# LB_BIT_i5_SLIDEDIMMER-v03_3_3.net
KiCad netlist of a schematic drawn in EAGLE
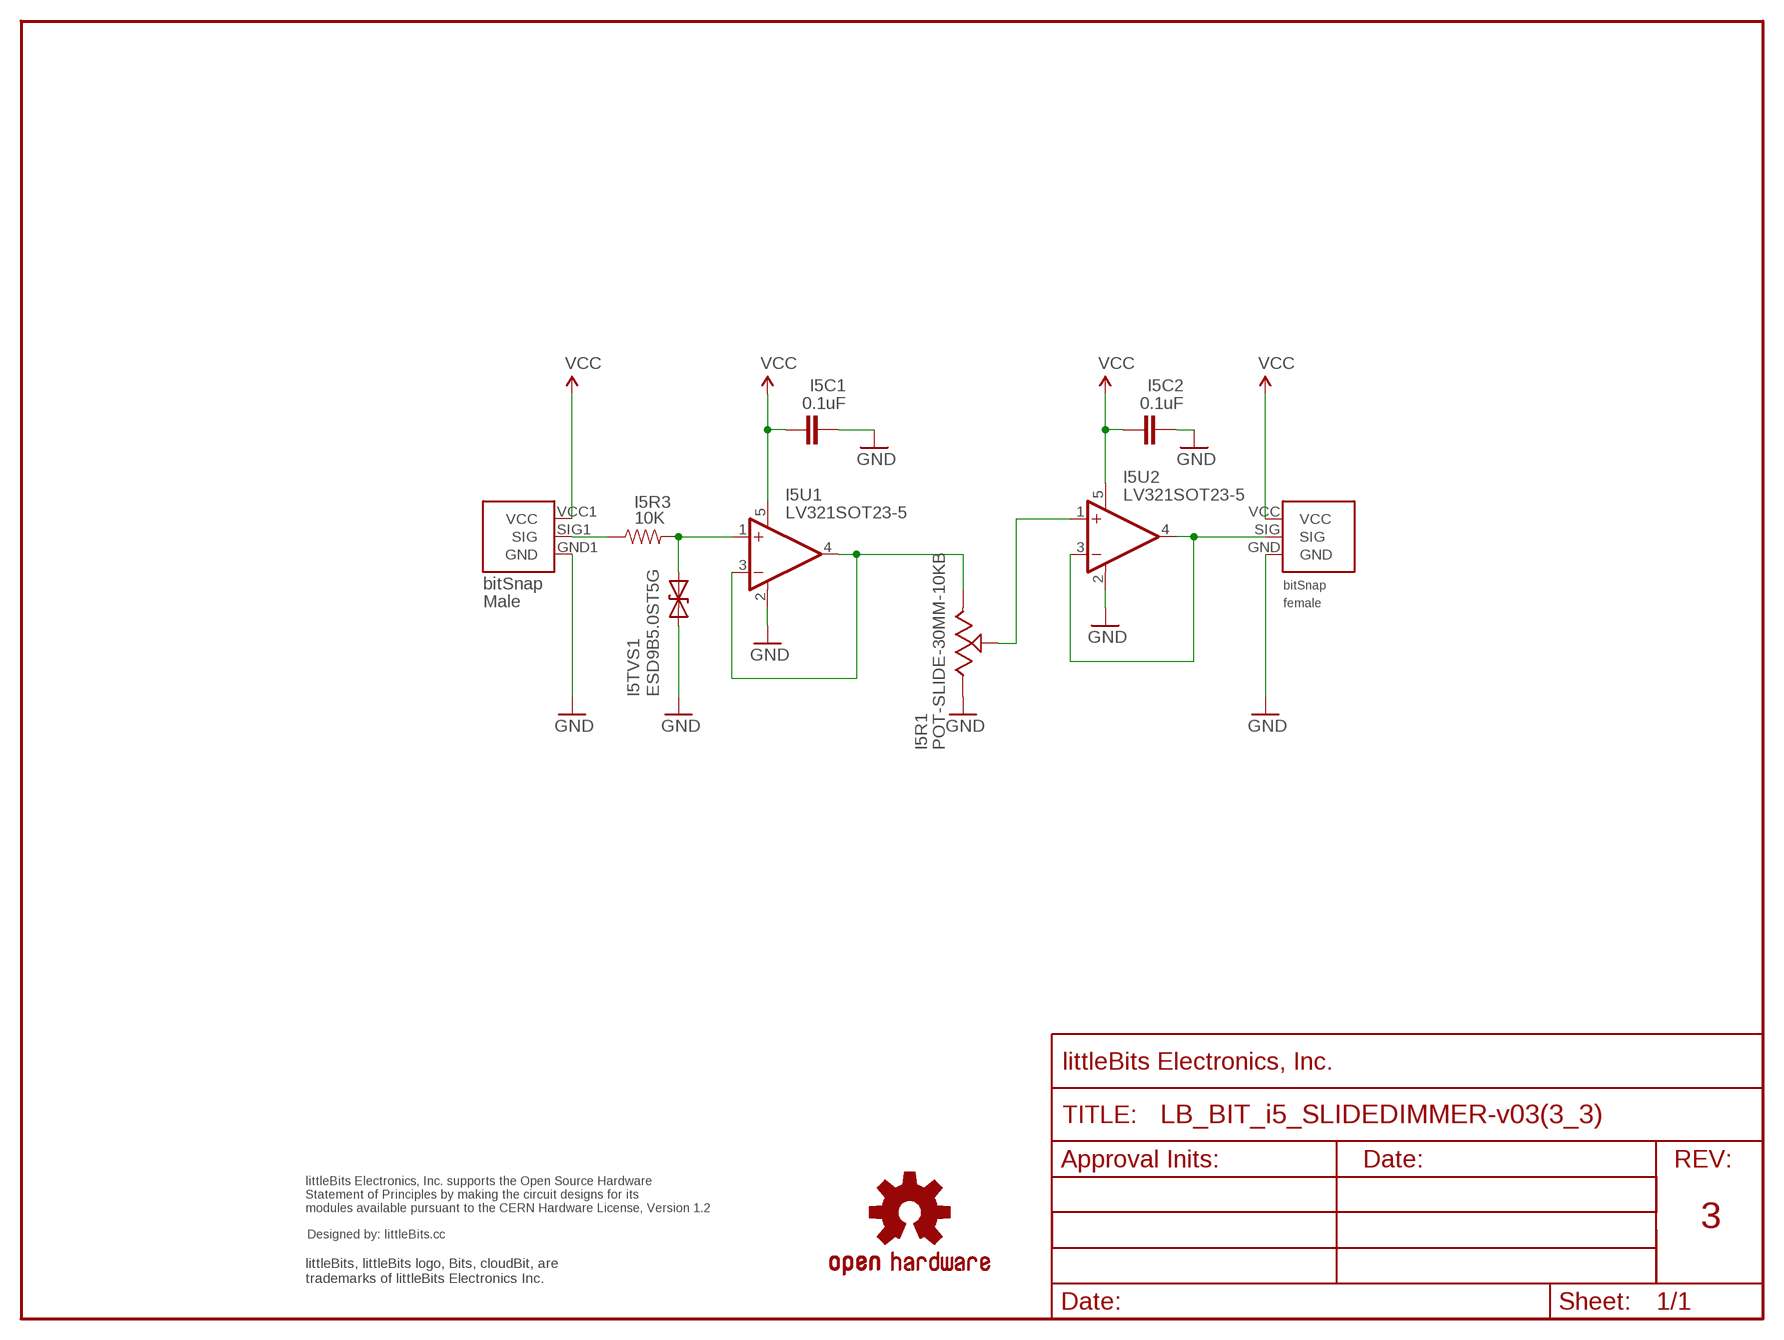
[diagram p0: schematic, sheet 1]

(export (version "E")
  (design (tool "Eeschema 10.0.6"))
  (components
    (comp (ref "FRAME2")
      (value "FRAME-LETTER-OHWOHW")
      (footprint "eagle-import:FABDWG01-OHW")
      (libsource (lib "eagle-import") (part "FRAME-LETTER-OHWOHW"))
    )
    (comp (ref "I5BSF1")
      (value "BITSNAP_V03_FEMALE")
      (footprint "eagle-import:BITSNAP_V03_FEMALE")
      (libsource (lib "eagle-import") (part "BITSNAP_V03_FEMALE"))
    )
    (comp (ref "I5BSM1")
      (value "BITSNAP_V03_MALE")
      (footprint "eagle-import:BITSNAP_V03_MALE")
      (libsource (lib "eagle-import") (part "BITSNAP_V03_MALE"))
    )
    (comp (ref "I5C1")
      (value "0.1uF")
      (footprint "eagle-import:CAP-0603")
      (libsource (lib "eagle-import") (part "CAPCAP-0603"))
    )
    (comp (ref "I5C2")
      (value "0.1uF")
      (footprint "eagle-import:CAP-0603")
      (libsource (lib "eagle-import") (part "CAPCAP-0603"))
    )
    (comp (ref "I5R1")
      (value "POT-SLIDE-30MM-10KB")
      (footprint "eagle-import:POT-SLIDE-30MM")
      (libsource (lib "eagle-import") (part "POT-SLIDE-30MM"))
    )
    (comp (ref "I5R3")
      (value "10K")
      (footprint "eagle-import:RES-0603")
      (libsource (lib "eagle-import") (part "RES-0603"))
    )
    (comp (ref "I5TVS1")
      (value "ESD9B5.0ST5G")
      (footprint "eagle-import:SOD-923")
      (libsource (lib "eagle-import") (part "DIODE-TVSSOD-923"))
    )
    (comp (ref "I5U1")
      (value "LV321SOT23-5")
      (footprint "eagle-import:SOT23-5")
      (libsource (lib "eagle-import") (part "LV321SOT23-5"))
    )
    (comp (ref "I5U2")
      (value "LV321SOT23-5")
      (footprint "eagle-import:SOT23-5")
      (libsource (lib "eagle-import") (part "LV321SOT23-5"))
    )
    (comp (ref "U$1")
      (value "OSHWCREDIT")
      (footprint "eagle-import:OSHWCREDIT")
      (libsource (lib "eagle-import") (part "OSHWCREDIT"))
    )
    (comp (ref "U$5")
      (value "OSHW-LOGOL")
      (footprint "eagle-import:OSHW-LOGO-L")
      (libsource (lib "eagle-import") (part "OSHW-LOGOL"))
    )
  )
  (nets
    (net (code "1") (name "GND") (class "Default")
      (node (ref "I5BSF1") (pin "GND") (pinfunction "GND_GND") (pintype "bidirectional"))
      (node (ref "I5BSM1") (pin "GND1") (pinfunction "GND_GND1") (pintype "bidirectional"))
      (node (ref "I5C1") (pin "2") (pinfunction "2_2") (pintype "passive"))
      (node (ref "I5C2") (pin "2") (pinfunction "2_2") (pintype "passive"))
      (node (ref "I5R1") (pin "3") (pinfunction "3_3") (pintype "passive"))
      (node (ref "I5TVS1") (pin "1") (pinfunction "A_1") (pintype "passive"))
      (node (ref "I5U1") (pin "2") (pinfunction "V-_2") (pintype "power_in"))
      (node (ref "I5U2") (pin "2") (pinfunction "V-_2") (pintype "power_in"))
    )
    (net (code "2") (name "Net-(I5BSM1-SIG)") (class "Default")
      (node (ref "I5BSM1") (pin "SIG1") (pinfunction "SIG_SIG1") (pintype "bidirectional"))
      (node (ref "I5R3") (pin "1") (pinfunction "1_1") (pintype "passive"))
    )
    (net (code "3") (name "Net-(I5TVS1-C)") (class "Default")
      (node (ref "I5R3") (pin "2") (pinfunction "2_2") (pintype "passive"))
      (node (ref "I5TVS1") (pin "2") (pinfunction "C_2") (pintype "passive"))
      (node (ref "I5U1") (pin "1") (pinfunction "+IN_1") (pintype "input"))
    )
    (net (code "4") (name "Net-(I5U1--IN)") (class "Default")
      (node (ref "I5R1") (pin "1") (pinfunction "1_1") (pintype "passive"))
      (node (ref "I5U1") (pin "3") (pinfunction "-IN_3") (pintype "input"))
      (node (ref "I5U1") (pin "4") (pinfunction "OUT_4") (pintype "output"))
    )
    (net (code "5") (name "Net-(I5U2-+IN)") (class "Default")
      (node (ref "I5R1") (pin "2") (pinfunction "2_2") (pintype "passive"))
      (node (ref "I5U2") (pin "1") (pinfunction "+IN_1") (pintype "input"))
    )
    (net (code "6") (name "Net-(I5U2--IN)") (class "Default")
      (node (ref "I5BSF1") (pin "SIG") (pinfunction "SIG_SIG") (pintype "bidirectional"))
      (node (ref "I5U2") (pin "3") (pinfunction "-IN_3") (pintype "input"))
      (node (ref "I5U2") (pin "4") (pinfunction "OUT_4") (pintype "output"))
    )
    (net (code "7") (name "VCC") (class "Default")
      (node (ref "I5BSF1") (pin "VCC") (pinfunction "VCC_VCC") (pintype "bidirectional"))
      (node (ref "I5BSM1") (pin "VCC1") (pinfunction "VCC_VCC1") (pintype "bidirectional"))
      (node (ref "I5C1") (pin "1") (pinfunction "1_1") (pintype "passive"))
      (node (ref "I5C2") (pin "1") (pinfunction "1_1") (pintype "passive"))
      (node (ref "I5U1") (pin "5") (pinfunction "V+_5") (pintype "power_in"))
      (node (ref "I5U2") (pin "5") (pinfunction "V+_5") (pintype "power_in"))
    )
  )
)
